# MiniMonitor_SCH.net
KiCad netlist of a schematic drawn in Altium Designer
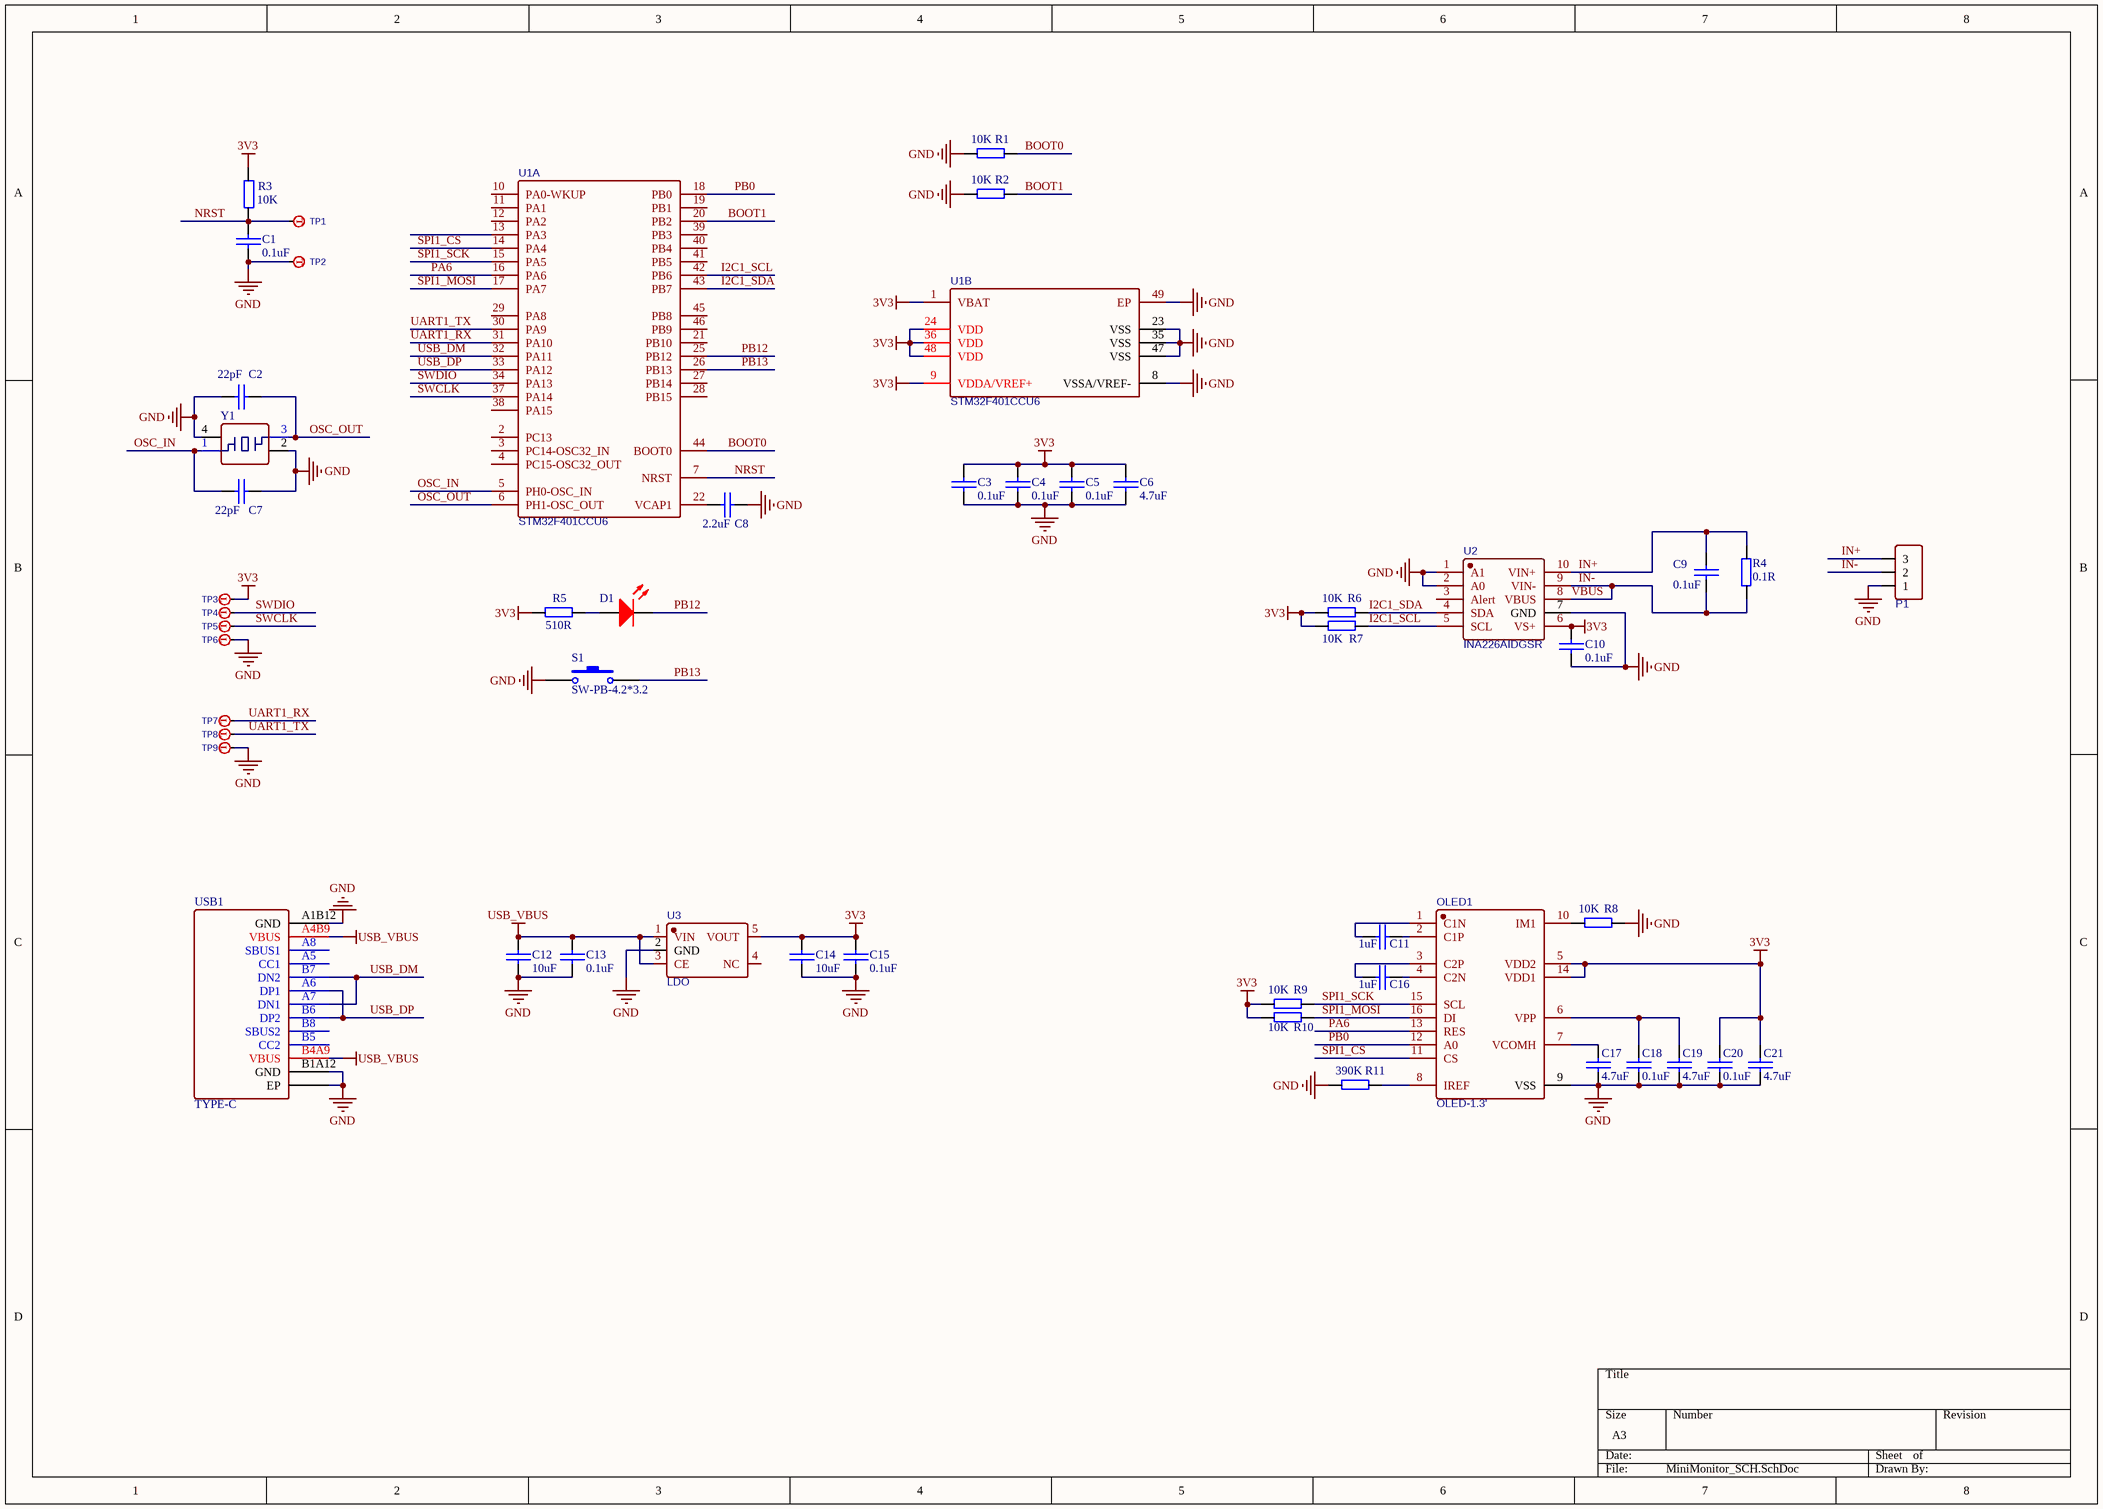
[diagram p0: MiniMonitor_SCH.SchDoc]

(export (version "E")
  (design (tool "Eeschema 10.0.6"))
  (components
    (comp (ref "C1") (value "0.1uF") (footprint "LC-0603_C") (libsource (lib "CJH_SCH") (part "CAP")))
    (comp (ref "C2") (value "22pF") (footprint "LC-0603_C") (libsource (lib "CJH_SCH") (part "CAP")))
    (comp (ref "C3") (value "0.1uF") (footprint "LC-0603_C") (libsource (lib "CJH_SCH") (part "CAP")))
    (comp (ref "C4") (value "0.1uF") (footprint "LC-0603_C") (libsource (lib "CJH_SCH") (part "CAP")))
    (comp (ref "C5") (value "0.1uF") (footprint "LC-0603_C") (libsource (lib "CJH_SCH") (part "CAP")))
    (comp (ref "C6") (value "4.7uF") (footprint "LC-0603_C") (libsource (lib "CJH_SCH") (part "CAP")))
    (comp (ref "C7") (value "22pF") (footprint "LC-0603_C") (libsource (lib "CJH_SCH") (part "CAP")))
    (comp (ref "C8") (value "2.2uF") (footprint "LC-0603_C") (libsource (lib "CJH_SCH") (part "CAP")))
    (comp (ref "C9") (value "0.1uF") (footprint "LC-0603_C") (libsource (lib "CJH_SCH") (part "CAP")))
    (comp (ref "C10") (value "0.1uF") (footprint "LC-0603_C") (libsource (lib "CJH_SCH") (part "CAP")))
    (comp (ref "C11") (value "1uF") (footprint "LC-0603_C") (libsource (lib "CJH_SCH") (part "CAP")))
    (comp (ref "C12") (value "10uF") (footprint "LC-0603_C") (libsource (lib "CJH_SCH") (part "CAP")))
    (comp (ref "C13") (value "0.1uF") (footprint "LC-0603_C") (libsource (lib "CJH_SCH") (part "CAP")))
    (comp (ref "C14") (value "10uF") (footprint "LC-0603_C") (libsource (lib "CJH_SCH") (part "CAP")))
    (comp (ref "C15") (value "0.1uF") (footprint "LC-0603_C") (libsource (lib "CJH_SCH") (part "CAP")))
    (comp (ref "C16") (value "1uF") (footprint "LC-0603_C") (libsource (lib "CJH_SCH") (part "CAP")))
    (comp (ref "C17") (value "4.7uF") (footprint "LC-0603_C") (libsource (lib "CJH_SCH") (part "CAP")))
    (comp (ref "C18") (value "0.1uF") (footprint "LC-0603_C") (libsource (lib "CJH_SCH") (part "CAP")))
    (comp (ref "C19") (value "4.7uF") (footprint "LC-0603_C") (libsource (lib "CJH_SCH") (part "CAP")))
    (comp (ref "C20") (value "0.1uF") (footprint "LC-0603_C") (libsource (lib "CJH_SCH") (part "CAP")))
    (comp (ref "C21") (value "4.7uF") (footprint "LC-0603_C") (libsource (lib "CJH_SCH") (part "CAP")))
    (comp (ref "D1")
      (value "LED_RED")
      (footprint "CJH_PCB:LC-0603_LED")
      (description "Typical INFRARED GaAs LED")
      (fields (field (name "PUBLISHER") "Altium Limited"))
      (libsource (lib "CJH_SCH") (part "LED_RED"))
    )
    (comp (ref "OLED1")
      (value "OLED-1.3'")
      (footprint "STM32F4:OLED-1.3")
      (fields
        (field (name "BOM_SUPPLIER PART") "C411031")
        (field (name "BOM_MANUFACTURER PART") "SSP7603P33M5R")
        (field (name "CONTRIBUTOR") "LCSC")
      )
      (libsource (lib "STM32F4") (part "OLED-1.3'"))
    )
    (comp (ref "P1")
      (value "HDR-F-2.54_1x3")
      (footprint "HDR1X3")
      (fields (field (name "BOM_SUPPLIER PART") "C146690") (field (name "CONTRIBUTOR") "LCEDA_Lib"))
      (libsource (lib "STM32F4") (part "HDR-F-2.54_1x3"))
    )
    (comp (ref "R1")
      (value "10K")
      (footprint "CJH_PCB:LC-0603_R")
      (libsource (lib "EXT_LEDMoudle_Pro") (part "R"))
    )
    (comp (ref "R2")
      (value "10K")
      (footprint "CJH_PCB:LC-0603_R")
      (libsource (lib "EXT_LEDMoudle_Pro") (part "R"))
    )
    (comp (ref "R3")
      (value "10K")
      (footprint "CJH_PCB:LC-0603_R")
      (libsource (lib "EXT_LEDMoudle_Pro") (part "R"))
    )
    (comp (ref "R4")
      (value "0.1R")
      (footprint "STM32F4:R2512")
      (libsource (lib "EXT_LEDMoudle_Pro") (part "R"))
    )
    (comp (ref "R5")
      (value "510R")
      (footprint "CJH_PCB:LC-0603_R")
      (libsource (lib "EXT_LEDMoudle_Pro") (part "R"))
    )
    (comp (ref "R6")
      (value "10K")
      (footprint "CJH_PCB:LC-0603_R")
      (libsource (lib "EXT_LEDMoudle_Pro") (part "R"))
    )
    (comp (ref "R7")
      (value "10K")
      (footprint "CJH_PCB:LC-0603_R")
      (libsource (lib "EXT_LEDMoudle_Pro") (part "R"))
    )
    (comp (ref "R8")
      (value "10K")
      (footprint "CJH_PCB:LC-0603_R")
      (libsource (lib "EXT_LEDMoudle_Pro") (part "R"))
    )
    (comp (ref "R9")
      (value "10K")
      (footprint "CJH_PCB:LC-0603_R")
      (libsource (lib "EXT_LEDMoudle_Pro") (part "R"))
    )
    (comp (ref "R10")
      (value "10K")
      (footprint "CJH_PCB:LC-0603_R")
      (libsource (lib "EXT_LEDMoudle_Pro") (part "R"))
    )
    (comp (ref "R11")
      (value "390K")
      (footprint "CJH_PCB:LC-0603_R")
      (libsource (lib "EXT_LEDMoudle_Pro") (part "R"))
    )
    (comp (ref "S1")
      (value "SW-PB-4.2*3.2")
      (footprint "CJH_PCB:SW  4.2*3.2")
      (description "Switch")
      (fields (field (name "PUBLISHER") "Altium Limited"))
      (libsource (lib "CJH_SCH") (part "SW-PB-4.2*3.2"))
    )
    (comp (ref "TP1") (value "TEST") (footprint "STM32F4:TEST") (libsource (lib "STM32F4") (part "TEST")))
    (comp (ref "TP2") (value "TEST") (footprint "STM32F4:TEST") (libsource (lib "STM32F4") (part "TEST")))
    (comp (ref "TP3") (value "TEST") (footprint "STM32F4:TEST") (libsource (lib "STM32F4") (part "TEST")))
    (comp (ref "TP4") (value "TEST") (footprint "STM32F4:TEST") (libsource (lib "STM32F4") (part "TEST")))
    (comp (ref "TP5") (value "TEST") (footprint "STM32F4:TEST") (libsource (lib "STM32F4") (part "TEST")))
    (comp (ref "TP6") (value "TEST") (footprint "STM32F4:TEST") (libsource (lib "STM32F4") (part "TEST")))
    (comp (ref "TP7") (value "TEST") (footprint "STM32F4:TEST") (libsource (lib "STM32F4") (part "TEST")))
    (comp (ref "TP8") (value "TEST") (footprint "STM32F4:TEST") (libsource (lib "STM32F4") (part "TEST")))
    (comp (ref "TP9") (value "TEST") (footprint "STM32F4:TEST") (libsource (lib "STM32F4") (part "TEST")))
    (comp (ref "U1")
      (value "STM32F401CCU6")
      (footprint "STM32F4:UFQFPN-48")
      (fields (field (name "BOM_SUPPLIER PART") "C79861") (field (name "SUBPART_NO") "2"))
      (libsource (lib "STM32F4") (part "STM32F401CCU6"))
    )
    (comp (ref "U2")
      (value "INA226AIDGSR")
      (footprint "STM32F4:MSOP10")
      (fields (field (name "BOM_SUPPLIER PART") "C49851"))
      (libsource (lib "STM32F4") (part "INA226AIDGSR"))
    )
    (comp (ref "U3")
      (value "LDO")
      (footprint "STM32F4:SOT23-5_S")
      (fields
        (field (name "BOM_SUPPLIER PART") "C411031")
        (field (name "BOM_MANUFACTURER PART") "SSP7603P33M5R")
        (field (name "CONTRIBUTOR") "LCSC")
      )
      (libsource (lib "STM32F4") (part "LDO"))
    )
    (comp (ref "USB1")
      (value "TYPE-C")
      (footprint "STM32F4:USB_TypeC2")
      (libsource (lib "STM32F4") (part "TYPE-C"))
    )
    (comp (ref "Y1")
      (value "CY3225")
      (footprint "STM32F4:OSC_3225")
      (libsource (lib "STM32F4") (part "CY3225"))
    )
  )
  (nets
    (net (code "1") (name "/BOOT0") (class "Default")
      (node (ref "R1") (pin "1") (pintype "passive"))
      (node (ref "U1") (pin "44") (pinfunction "BOOT0_44") (pintype "passive"))
    )
    (net (code "2") (name "/BOOT1") (class "Default")
      (node (ref "R2") (pin "1") (pintype "passive"))
      (node (ref "U1") (pin "20") (pinfunction "PB2_20") (pintype "passive"))
    )
    (net (code "3") (name "/I2C1_SCL") (class "Default")
      (node (ref "R7") (pin "1") (pintype "passive"))
      (node (ref "U1") (pin "42") (pinfunction "PB6_42") (pintype "passive"))
      (node (ref "U2") (pin "5") (pinfunction "SCL_5") (pintype "passive"))
    )
    (net (code "4") (name "/I2C1_SDA") (class "Default")
      (node (ref "R6") (pin "1") (pintype "passive"))
      (node (ref "U1") (pin "43") (pinfunction "PB7_43") (pintype "passive"))
      (node (ref "U2") (pin "4") (pinfunction "SDA_4") (pintype "passive"))
    )
    (net (code "5") (name "/IN+") (class "Default")
      (node (ref "C9") (pin "1") (pinfunction "1_1") (pintype "passive"))
      (node (ref "P1") (pin "3") (pinfunction "3_3") (pintype "passive"))
      (node (ref "R4") (pin "1") (pintype "passive"))
      (node (ref "U2") (pin "10") (pinfunction "VIN+_10") (pintype "passive"))
    )
    (net (code "6") (name "/IN-") (class "Default")
      (node (ref "C9") (pin "2") (pinfunction "2_2") (pintype "passive"))
      (node (ref "P1") (pin "2") (pinfunction "2_2") (pintype "passive"))
      (node (ref "R4") (pin "2") (pintype "passive"))
      (node (ref "U2") (pin "8") (pinfunction "VBUS_8") (pintype "passive"))
      (node (ref "U2") (pin "9") (pinfunction "VIN-_9") (pintype "passive"))
    )
    (net (code "7") (name "/NRST") (class "Default")
      (node (ref "C1") (pin "2") (pinfunction "2_2") (pintype "passive"))
      (node (ref "R3") (pin "1") (pintype "passive"))
      (node (ref "TP1") (pin "1") (pinfunction "1_1") (pintype "passive"))
      (node (ref "U1") (pin "7") (pinfunction "NRST_7") (pintype "passive"))
    )
    (net (code "8") (name "/OSC_IN") (class "Default")
      (node (ref "C7") (pin "1") (pinfunction "1_1") (pintype "passive"))
      (node (ref "U1") (pin "5") (pinfunction "PH0-OSC_IN_5") (pintype "passive"))
      (node (ref "Y1") (pin "1") (pinfunction "1_1") (pintype "passive"))
    )
    (net (code "9") (name "/OSC_OUT") (class "Default")
      (node (ref "C2") (pin "2") (pinfunction "2_2") (pintype "passive"))
      (node (ref "U1") (pin "6") (pinfunction "PH1-OSC_OUT_6") (pintype "passive"))
      (node (ref "Y1") (pin "3") (pinfunction "3_3") (pintype "passive"))
    )
    (net (code "10") (name "/PA6") (class "Default")
      (node (ref "OLED1") (pin "13") (pinfunction "RES_13") (pintype "passive"))
      (node (ref "U1") (pin "16") (pinfunction "PA6_16") (pintype "passive"))
    )
    (net (code "11") (name "/PB0") (class "Default")
      (node (ref "OLED1") (pin "12") (pinfunction "A0_12") (pintype "passive"))
      (node (ref "U1") (pin "18") (pinfunction "PB0_18") (pintype "passive"))
    )
    (net (code "12") (name "/PB12") (class "Default")
      (node (ref "D1") (pin "K") (pinfunction "K_K") (pintype "passive"))
      (node (ref "U1") (pin "25") (pinfunction "PB12_25") (pintype "passive"))
    )
    (net (code "13") (name "/PB13") (class "Default")
      (node (ref "S1") (pin "2") (pinfunction "2_2") (pintype "passive"))
      (node (ref "U1") (pin "26") (pinfunction "PB13_26") (pintype "passive"))
    )
    (net (code "14") (name "/SPI1_CS") (class "Default")
      (node (ref "OLED1") (pin "11") (pinfunction "CS_11") (pintype "passive"))
      (node (ref "U1") (pin "14") (pinfunction "PA4_14") (pintype "passive"))
    )
    (net (code "15") (name "/SPI1_MOSI") (class "Default")
      (node (ref "OLED1") (pin "16") (pinfunction "DI_16") (pintype "passive"))
      (node (ref "R10") (pin "1") (pintype "passive"))
      (node (ref "U1") (pin "17") (pinfunction "PA7_17") (pintype "passive"))
    )
    (net (code "16") (name "/SPI1_SCK") (class "Default")
      (node (ref "OLED1") (pin "15") (pinfunction "SCL_15") (pintype "passive"))
      (node (ref "R9") (pin "1") (pintype "passive"))
      (node (ref "U1") (pin "15") (pinfunction "PA5_15") (pintype "passive"))
    )
    (net (code "17") (name "/SWCLK") (class "Default")
      (node (ref "TP5") (pin "1") (pinfunction "1_1") (pintype "passive"))
      (node (ref "U1") (pin "37") (pinfunction "PA14_37") (pintype "passive"))
    )
    (net (code "18") (name "/SWDIO") (class "Default")
      (node (ref "TP4") (pin "1") (pinfunction "1_1") (pintype "passive"))
      (node (ref "U1") (pin "34") (pinfunction "PA13_34") (pintype "passive"))
    )
    (net (code "19") (name "/UART1_RX") (class "Default")
      (node (ref "TP7") (pin "1") (pinfunction "1_1") (pintype "passive"))
      (node (ref "U1") (pin "31") (pinfunction "PA10_31") (pintype "passive"))
    )
    (net (code "20") (name "/UART1_TX") (class "Default")
      (node (ref "TP8") (pin "1") (pinfunction "1_1") (pintype "passive"))
      (node (ref "U1") (pin "30") (pinfunction "PA9_30") (pintype "passive"))
    )
    (net (code "21") (name "/USB_DM") (class "Default")
      (node (ref "U1") (pin "32") (pinfunction "PA11_32") (pintype "passive"))
      (node (ref "USB1") (pin "A7") (pinfunction "DN1_A7") (pintype "passive"))
      (node (ref "USB1") (pin "B7") (pinfunction "DN2_B7") (pintype "passive"))
    )
    (net (code "22") (name "/USB_DP") (class "Default")
      (node (ref "U1") (pin "33") (pinfunction "PA12_33") (pintype "passive"))
      (node (ref "USB1") (pin "A6") (pinfunction "DP1_A6") (pintype "passive"))
      (node (ref "USB1") (pin "B6") (pinfunction "DP2_B6") (pintype "passive"))
    )
    (net (code "23") (name "3V3") (class "Default")
      (node (ref "C10") (pin "2") (pinfunction "2_2") (pintype "passive"))
      (node (ref "C14") (pin "2") (pinfunction "2_2") (pintype "passive"))
      (node (ref "C15") (pin "2") (pinfunction "2_2") (pintype "passive"))
      (node (ref "C20") (pin "2") (pinfunction "2_2") (pintype "passive"))
      (node (ref "C21") (pin "2") (pinfunction "2_2") (pintype "passive"))
      (node (ref "C3") (pin "2") (pinfunction "2_2") (pintype "passive"))
      (node (ref "C4") (pin "2") (pinfunction "2_2") (pintype "passive"))
      (node (ref "C5") (pin "2") (pinfunction "2_2") (pintype "passive"))
      (node (ref "C6") (pin "2") (pinfunction "2_2") (pintype "passive"))
      (node (ref "OLED1") (pin "14") (pinfunction "VDD1_14") (pintype "passive"))
      (node (ref "OLED1") (pin "5") (pinfunction "VDD2_5") (pintype "passive"))
      (node (ref "R10") (pin "2") (pintype "passive"))
      (node (ref "R3") (pin "2") (pintype "passive"))
      (node (ref "R5") (pin "2") (pintype "passive"))
      (node (ref "R6") (pin "2") (pintype "passive"))
      (node (ref "R7") (pin "2") (pintype "passive"))
      (node (ref "R9") (pin "2") (pintype "passive"))
      (node (ref "TP3") (pin "1") (pinfunction "1_1") (pintype "passive"))
      (node (ref "U1") (pin "1") (pinfunction "VBAT_1") (pintype "passive"))
      (node (ref "U1") (pin "24") (pinfunction "VDD_24") (pintype "passive"))
      (node (ref "U1") (pin "36") (pinfunction "VDD_36") (pintype "passive"))
      (node (ref "U1") (pin "48") (pinfunction "VDD_48") (pintype "passive"))
      (node (ref "U1") (pin "9") (pinfunction "VDDA/VREF+_9") (pintype "passive"))
      (node (ref "U2") (pin "6") (pinfunction "VS+_6") (pintype "passive"))
      (node (ref "U3") (pin "5") (pinfunction "VOUT_5") (pintype "passive"))
    )
    (net (code "24") (name "GND") (class "Default")
      (node (ref "C1") (pin "1") (pinfunction "1_1") (pintype "passive"))
      (node (ref "C10") (pin "1") (pinfunction "1_1") (pintype "passive"))
      (node (ref "C12") (pin "1") (pinfunction "1_1") (pintype "passive"))
      (node (ref "C13") (pin "1") (pinfunction "1_1") (pintype "passive"))
      (node (ref "C14") (pin "1") (pinfunction "1_1") (pintype "passive"))
      (node (ref "C15") (pin "1") (pinfunction "1_1") (pintype "passive"))
      (node (ref "C17") (pin "1") (pinfunction "1_1") (pintype "passive"))
      (node (ref "C18") (pin "1") (pinfunction "1_1") (pintype "passive"))
      (node (ref "C19") (pin "1") (pinfunction "1_1") (pintype "passive"))
      (node (ref "C2") (pin "1") (pinfunction "1_1") (pintype "passive"))
      (node (ref "C20") (pin "1") (pinfunction "1_1") (pintype "passive"))
      (node (ref "C21") (pin "1") (pinfunction "1_1") (pintype "passive"))
      (node (ref "C3") (pin "1") (pinfunction "1_1") (pintype "passive"))
      (node (ref "C4") (pin "1") (pinfunction "1_1") (pintype "passive"))
      (node (ref "C5") (pin "1") (pinfunction "1_1") (pintype "passive"))
      (node (ref "C6") (pin "1") (pinfunction "1_1") (pintype "passive"))
      (node (ref "C7") (pin "2") (pinfunction "2_2") (pintype "passive"))
      (node (ref "C8") (pin "2") (pinfunction "2_2") (pintype "passive"))
      (node (ref "OLED1") (pin "9") (pinfunction "VSS_9") (pintype "passive"))
      (node (ref "P1") (pin "1") (pinfunction "1_1") (pintype "passive"))
      (node (ref "R1") (pin "2") (pintype "passive"))
      (node (ref "R11") (pin "2") (pintype "passive"))
      (node (ref "R2") (pin "2") (pintype "passive"))
      (node (ref "R8") (pin "1") (pintype "passive"))
      (node (ref "S1") (pin "1") (pinfunction "1_1") (pintype "passive"))
      (node (ref "TP2") (pin "1") (pinfunction "1_1") (pintype "passive"))
      (node (ref "TP6") (pin "1") (pinfunction "1_1") (pintype "passive"))
      (node (ref "TP9") (pin "1") (pinfunction "1_1") (pintype "passive"))
      (node (ref "U1") (pin "23") (pinfunction "VSS_23") (pintype "passive"))
      (node (ref "U1") (pin "35") (pinfunction "VSS_35") (pintype "passive"))
      (node (ref "U1") (pin "47") (pinfunction "VSS_47") (pintype "passive"))
      (node (ref "U1") (pin "49") (pinfunction "EP_49") (pintype "passive"))
      (node (ref "U1") (pin "8") (pinfunction "VSSA/VREF-_8") (pintype "passive"))
      (node (ref "U2") (pin "1") (pinfunction "A1_1") (pintype "passive"))
      (node (ref "U2") (pin "2") (pinfunction "A0_2") (pintype "passive"))
      (node (ref "U2") (pin "7") (pinfunction "GND_7") (pintype "passive"))
      (node (ref "U3") (pin "2") (pinfunction "GND_2") (pintype "passive"))
      (node (ref "USB1") (pin "1") (pinfunction "EP_1") (pintype "passive"))
      (node (ref "USB1") (pin "A1B12") (pinfunction "GND_A1B12") (pintype "passive"))
      (node (ref "USB1") (pin "B1A12") (pinfunction "GND_B1A12") (pintype "passive"))
      (node (ref "Y1") (pin "2") (pinfunction "2_2") (pintype "passive"))
      (node (ref "Y1") (pin "4") (pinfunction "4_4") (pintype "passive"))
    )
    (net (code "25") (name "Net-(D1-PadA)") (class "Default")
      (node (ref "D1") (pin "A") (pinfunction "A_A") (pintype "passive"))
      (node (ref "R5") (pin "1") (pintype "passive"))
    )
    (net (code "26") (name "Net-(OLED1-C1N)") (class "Default")
      (node (ref "C11") (pin "2") (pinfunction "2_2") (pintype "passive"))
      (node (ref "OLED1") (pin "1") (pinfunction "C1N_1") (pintype "passive"))
    )
    (net (code "27") (name "Net-(OLED1-C1P)") (class "Default")
      (node (ref "C11") (pin "1") (pinfunction "1_1") (pintype "passive"))
      (node (ref "OLED1") (pin "2") (pinfunction "C1P_2") (pintype "passive"))
    )
    (net (code "28") (name "Net-(OLED1-C2N)") (class "Default")
      (node (ref "C16") (pin "1") (pinfunction "1_1") (pintype "passive"))
      (node (ref "OLED1") (pin "4") (pinfunction "C2N_4") (pintype "passive"))
    )
    (net (code "29") (name "Net-(OLED1-C2P)") (class "Default")
      (node (ref "C16") (pin "2") (pinfunction "2_2") (pintype "passive"))
      (node (ref "OLED1") (pin "3") (pinfunction "C2P_3") (pintype "passive"))
    )
    (net (code "30") (name "Net-(OLED1-IM1)") (class "Default")
      (node (ref "OLED1") (pin "10") (pinfunction "IM1_10") (pintype "passive"))
      (node (ref "R8") (pin "2") (pintype "passive"))
    )
    (net (code "31") (name "Net-(OLED1-IREF)") (class "Default")
      (node (ref "OLED1") (pin "8") (pinfunction "IREF_8") (pintype "passive"))
      (node (ref "R11") (pin "1") (pintype "passive"))
    )
    (net (code "32") (name "Net-(OLED1-VCOMH)") (class "Default")
      (node (ref "C17") (pin "2") (pinfunction "2_2") (pintype "passive"))
      (node (ref "OLED1") (pin "7") (pinfunction "VCOMH_7") (pintype "passive"))
    )
    (net (code "33") (name "Net-(OLED1-VPP)") (class "Default")
      (node (ref "C18") (pin "2") (pinfunction "2_2") (pintype "passive"))
      (node (ref "C19") (pin "2") (pinfunction "2_2") (pintype "passive"))
      (node (ref "OLED1") (pin "6") (pinfunction "VPP_6") (pintype "passive"))
    )
    (net (code "34") (name "Net-(U1A-VCAP1)") (class "Default")
      (node (ref "C8") (pin "1") (pinfunction "1_1") (pintype "passive"))
      (node (ref "U1") (pin "22") (pinfunction "VCAP1_22") (pintype "passive"))
    )
    (net (code "35") (name "USB_VBUS") (class "Default")
      (node (ref "C12") (pin "2") (pinfunction "2_2") (pintype "passive"))
      (node (ref "C13") (pin "2") (pinfunction "2_2") (pintype "passive"))
      (node (ref "U3") (pin "1") (pinfunction "VIN_1") (pintype "passive"))
      (node (ref "U3") (pin "3") (pinfunction "CE_3") (pintype "passive"))
      (node (ref "USB1") (pin "A4B9") (pinfunction "VBUS_A4B9") (pintype "passive"))
      (node (ref "USB1") (pin "B4A9") (pinfunction "VBUS_B4A9") (pintype "passive"))
    )
    (net (code "36") (name "unconnected-(U1A-PA0-WKUP-Pad10)") (class "Default")
      (node (ref "U1") (pin "10") (pinfunction "PA0-WKUP_10") (pintype "passive"))
    )
    (net (code "37") (name "unconnected-(U1A-PA1-Pad11)") (class "Default")
      (node (ref "U1") (pin "11") (pinfunction "PA1_11") (pintype "passive"))
    )
    (net (code "38") (name "unconnected-(U1A-PA2-Pad12)") (class "Default")
      (node (ref "U1") (pin "12") (pinfunction "PA2_12") (pintype "passive"))
    )
    (net (code "39") (name "unconnected-(U1A-PA3-Pad13)") (class "Default")
      (node (ref "U1") (pin "13") (pinfunction "PA3_13") (pintype "passive"))
    )
    (net (code "40") (name "unconnected-(U1A-PA8-Pad29)") (class "Default")
      (node (ref "U1") (pin "29") (pinfunction "PA8_29") (pintype "passive"))
    )
    (net (code "41") (name "unconnected-(U1A-PA15-Pad38)") (class "Default")
      (node (ref "U1") (pin "38") (pinfunction "PA15_38") (pintype "passive"))
    )
    (net (code "42") (name "unconnected-(U1A-PB1-Pad19)") (class "Default")
      (node (ref "U1") (pin "19") (pinfunction "PB1_19") (pintype "passive"))
    )
    (net (code "43") (name "unconnected-(U1A-PB3-Pad39)") (class "Default")
      (node (ref "U1") (pin "39") (pinfunction "PB3_39") (pintype "passive"))
    )
    (net (code "44") (name "unconnected-(U1A-PB4-Pad40)") (class "Default")
      (node (ref "U1") (pin "40") (pinfunction "PB4_40") (pintype "passive"))
    )
    (net (code "45") (name "unconnected-(U1A-PB5-Pad41)") (class "Default")
      (node (ref "U1") (pin "41") (pinfunction "PB5_41") (pintype "passive"))
    )
    (net (code "46") (name "unconnected-(U1A-PB8-Pad45)") (class "Default")
      (node (ref "U1") (pin "45") (pinfunction "PB8_45") (pintype "passive"))
    )
    (net (code "47") (name "unconnected-(U1A-PB9-Pad46)") (class "Default")
      (node (ref "U1") (pin "46") (pinfunction "PB9_46") (pintype "passive"))
    )
    (net (code "48") (name "unconnected-(U1A-PB10-Pad21)") (class "Default")
      (node (ref "U1") (pin "21") (pinfunction "PB10_21") (pintype "passive"))
    )
    (net (code "49") (name "unconnected-(U1A-PB14-Pad27)") (class "Default")
      (node (ref "U1") (pin "27") (pinfunction "PB14_27") (pintype "passive"))
    )
    (net (code "50") (name "unconnected-(U1A-PB15-Pad28)") (class "Default")
      (node (ref "U1") (pin "28") (pinfunction "PB15_28") (pintype "passive"))
    )
    (net (code "51") (name "unconnected-(U1A-PC13-Pad2)") (class "Default")
      (node (ref "U1") (pin "2") (pinfunction "PC13_2") (pintype "passive"))
    )
    (net (code "52") (name "unconnected-(U1A-PC14-OSC32_IN-Pad3)") (class "Default")
      (node (ref "U1") (pin "3") (pinfunction "PC14-OSC32_IN_3") (pintype "passive"))
    )
    (net (code "53") (name "unconnected-(U1A-PC15-OSC32_OUT-Pad4)") (class "Default")
      (node (ref "U1") (pin "4") (pinfunction "PC15-OSC32_OUT_4") (pintype "passive"))
    )
    (net (code "54") (name "unconnected-(U2-Alert-Pad3)") (class "Default")
      (node (ref "U2") (pin "3") (pinfunction "Alert_3") (pintype "passive"))
    )
    (net (code "55") (name "unconnected-(U3-NC-Pad4)") (class "Default")
      (node (ref "U3") (pin "4") (pinfunction "NC_4") (pintype "passive"))
    )
    (net (code "56") (name "unconnected-(USB1-CC1-PadA5)") (class "Default")
      (node (ref "USB1") (pin "A5") (pinfunction "CC1_A5") (pintype "passive"))
    )
    (net (code "57") (name "unconnected-(USB1-CC2-PadB5)") (class "Default")
      (node (ref "USB1") (pin "B5") (pinfunction "CC2_B5") (pintype "passive"))
    )
    (net (code "58") (name "unconnected-(USB1-SBUS1-PadA8)") (class "Default")
      (node (ref "USB1") (pin "A8") (pinfunction "SBUS1_A8") (pintype "passive"))
    )
    (net (code "59") (name "unconnected-(USB1-SBUS2-PadB8)") (class "Default")
      (node (ref "USB1") (pin "B8") (pinfunction "SBUS2_B8") (pintype "passive"))
    )
  )
)
